# SonarControl.net
KiCad netlist of a schematic drawn in Altium Designer
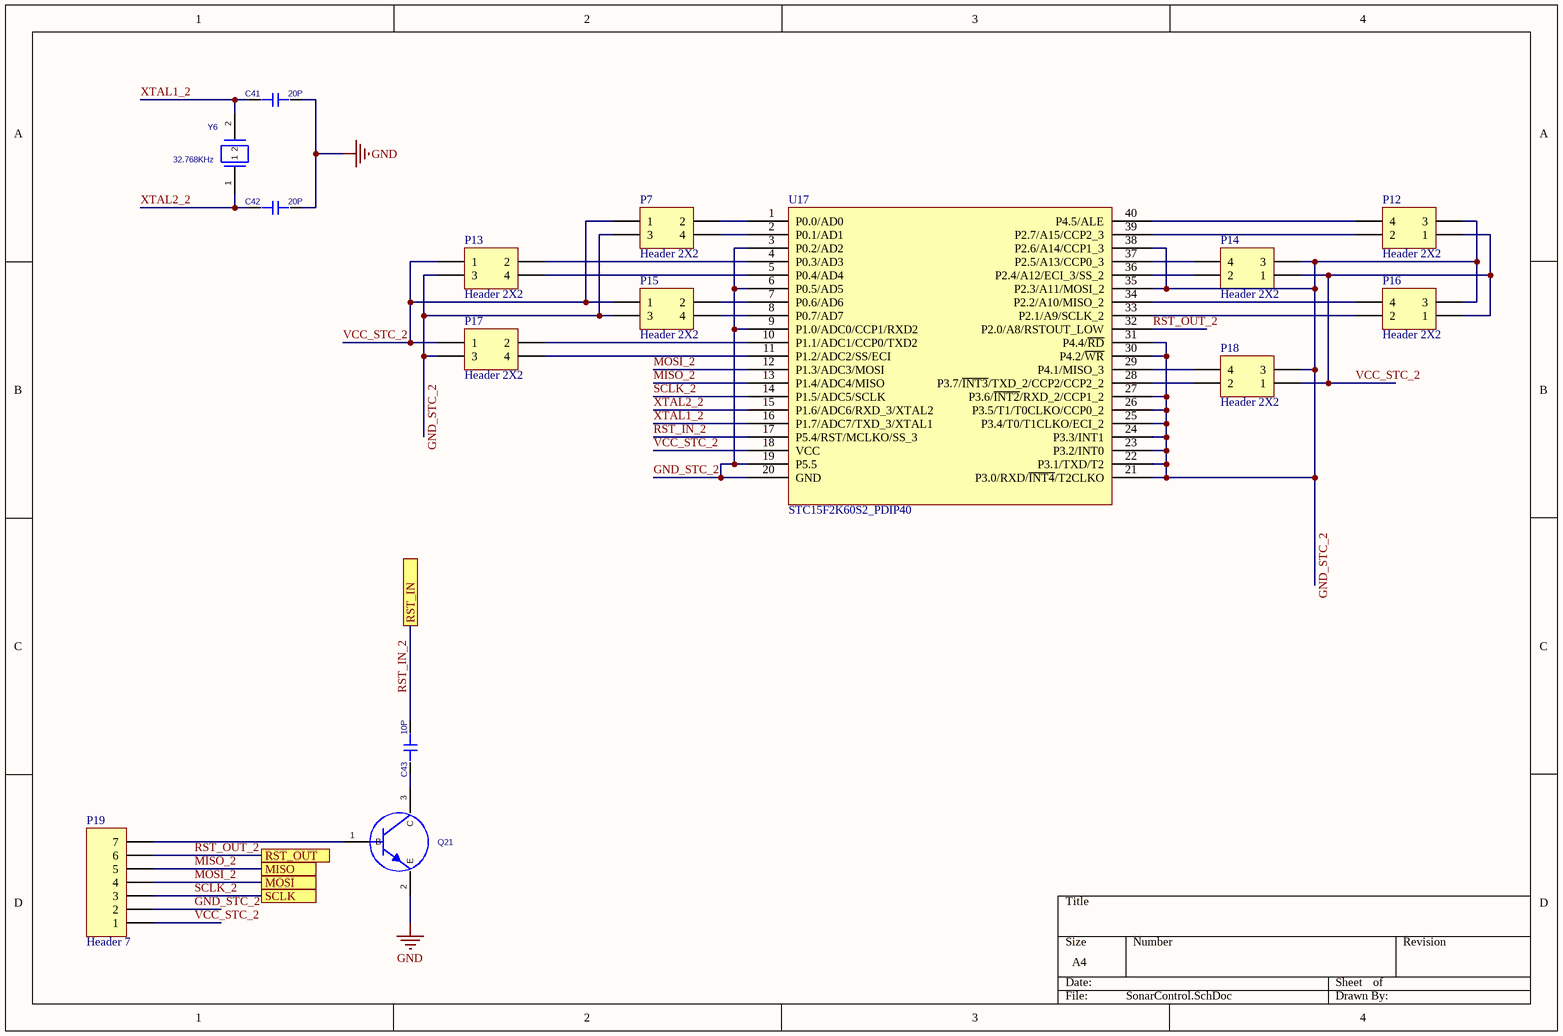
[diagram p0: SonarControl.SchDoc]

(export (version "E")
  (design (tool "Eeschema 10.0.6"))
  (components
    (comp (ref "C41")
      (value "20P")
      (footprint "CAP_0603_FIRE")
      (fields (field (name "Comment") "CAP_20P_0603_FIRE"))
      (libsource (lib "MINI-V3") (part "CAP_20P_0603_FIRE"))
    )
    (comp (ref "C42")
      (value "20P")
      (footprint "CAP_0603_FIRE")
      (fields (field (name "Comment") "CAP_20P_0603_FIRE"))
      (libsource (lib "MINI-V3") (part "CAP_20P_0603_FIRE"))
    )
    (comp (ref "C43")
      (value "10P")
      (footprint "RES_0603_FIRE")
      (description "0603")
      (fields (field (name "TOLERANCE") "+-5%") (field (name "Comment") "CAP_10P_0603_FIRE"))
      (libsource (lib "MINI-V3") (part "CAP_10P_0603_FIRE"))
    )
    (comp (ref "P7")
      (value "Header 2X2")
      (footprint "HDR2X2")
      (description "Header, 2-Pin, Dual row")
      (fields (field (name "PUBLISHER") "Altium Limited"))
      (libsource (lib "插针") (part "Header 2X2"))
    )
    (comp (ref "P12")
      (value "Header 2X2")
      (footprint "HDR2X2")
      (description "Header, 2-Pin, Dual row")
      (fields (field (name "PUBLISHER") "Altium Limited"))
      (libsource (lib "") (part "Header 2X2_1"))
    )
    (comp (ref "P13")
      (value "Header 2X2")
      (footprint "HDR2X2")
      (description "Header, 2-Pin, Dual row")
      (fields (field (name "PUBLISHER") "Altium Limited"))
      (libsource (lib "插针") (part "Header 2X2"))
    )
    (comp (ref "P14")
      (value "Header 2X2")
      (footprint "HDR2X2")
      (description "Header, 2-Pin, Dual row")
      (fields (field (name "PUBLISHER") "Altium Limited"))
      (libsource (lib "") (part "Header 2X2_1"))
    )
    (comp (ref "P15")
      (value "Header 2X2")
      (footprint "HDR2X2")
      (description "Header, 2-Pin, Dual row")
      (fields (field (name "PUBLISHER") "Altium Limited"))
      (libsource (lib "插针") (part "Header 2X2"))
    )
    (comp (ref "P16")
      (value "Header 2X2")
      (footprint "HDR2X2")
      (description "Header, 2-Pin, Dual row")
      (fields (field (name "PUBLISHER") "Altium Limited"))
      (libsource (lib "") (part "Header 2X2_1"))
    )
    (comp (ref "P17")
      (value "Header 2X2")
      (footprint "HDR2X2")
      (description "Header, 2-Pin, Dual row")
      (fields (field (name "PUBLISHER") "Altium Limited"))
      (libsource (lib "插针") (part "Header 2X2"))
    )
    (comp (ref "P18")
      (value "Header 2X2")
      (footprint "HDR2X2")
      (description "Header, 2-Pin, Dual row")
      (fields (field (name "PUBLISHER") "Altium Limited"))
      (libsource (lib "") (part "Header 2X2_1"))
    )
    (comp (ref "P19")
      (value "Header 7")
      (description "Header, 7-Pin")
      (fields (field (name "PUBLISHER") "Altium Limited"))
      (libsource (lib "插针") (part "Header 7"))
    )
    (comp (ref "Q21")
      (value "8050")
      (footprint "SOT-23")
      (description "NPN")
      (libsource (lib "MINI-V3") (part "8050"))
    )
    (comp (ref "U17")
      (value "STC15F2K60S2_PDIP40")
      (footprint "DIP40")
      (libsource (lib "STCMCU") (part "STC15F2K60S2_PDIP40"))
    )
    (comp (ref "Y6")
      (value "32.768KHz")
      (footprint "3215")
      (description "CRYSTAL")
      (fields (field (name "Comment") "XTAL_32.768KHZ_3215"))
      (libsource (lib "MINI-V3") (part "XTAL_32.768KHZ_3215"))
    )
  )
  (nets
    (net (code "1") (name "/GND_STC_2") (class "Default")
      (node (ref "P12") (pin "3") (pinfunction "3_3") (pintype "passive"))
      (node (ref "P13") (pin "3") (pinfunction "3_3") (pintype "passive"))
      (node (ref "P14") (pin "3") (pinfunction "3_3") (pintype "passive"))
      (node (ref "P15") (pin "3") (pinfunction "3_3") (pintype "passive"))
      (node (ref "P16") (pin "3") (pinfunction "3_3") (pintype "passive"))
      (node (ref "P17") (pin "3") (pinfunction "3_3") (pintype "passive"))
      (node (ref "P18") (pin "3") (pinfunction "3_3") (pintype "passive"))
      (node (ref "P19") (pin "2") (pinfunction "2_2") (pintype "passive"))
      (node (ref "P7") (pin "3") (pinfunction "3_3") (pintype "passive"))
      (node (ref "U17") (pin "19") (pinfunction "P5.5_19") (pintype "passive"))
      (node (ref "U17") (pin "20") (pinfunction "GND_20") (pintype "passive"))
      (node (ref "U17") (pin "21") (pinfunction "P3.0/RXD/~{INT4}/T2CLKO_21") (pintype "passive"))
      (node (ref "U17") (pin "22") (pinfunction "P3.1/TXD/T2_22") (pintype "passive"))
      (node (ref "U17") (pin "23") (pinfunction "P3.2/INT0_23") (pintype "passive"))
      (node (ref "U17") (pin "24") (pinfunction "P3.3/INT1_24") (pintype "passive"))
      (node (ref "U17") (pin "25") (pinfunction "P3.4/T0/T1CLKO/ECI_2_25") (pintype "passive"))
      (node (ref "U17") (pin "26") (pinfunction "P3.5/T1/T0CLKO/CCP0_2_26") (pintype "passive"))
      (node (ref "U17") (pin "27") (pinfunction "P3.6/~{INT2}/RXD_2/CCP1_2_27") (pintype "passive"))
      (node (ref "U17") (pin "3") (pinfunction "P0.2/AD2_3") (pintype "passive"))
      (node (ref "U17") (pin "30") (pinfunction "P4.2/~{WR}_30") (pintype "passive"))
      (node (ref "U17") (pin "31") (pinfunction "P4.4/~{RD}_31") (pintype "passive"))
      (node (ref "U17") (pin "35") (pinfunction "P2.3/A11/MOSI_2_35") (pintype "passive"))
      (node (ref "U17") (pin "38") (pinfunction "P2.6/A14/CCP1_3_38") (pintype "passive"))
      (node (ref "U17") (pin "6") (pinfunction "P0.5/AD5_6") (pintype "passive"))
      (node (ref "U17") (pin "9") (pinfunction "P1.0/ADC0/CCP1/RXD2_9") (pintype "passive"))
    )
    (net (code "2") (name "/MISO_2") (class "Default")
      (node (ref "P19") (pin "5") (pinfunction "5_5") (pintype "passive"))
      (node (ref "U17") (pin "13") (pinfunction "P1.4/ADC4/MISO_13") (pintype "passive"))
    )
    (net (code "3") (name "/MOSI_2") (class "Default")
      (node (ref "P19") (pin "4") (pinfunction "4_4") (pintype "passive"))
      (node (ref "U17") (pin "12") (pinfunction "P1.3/ADC3/MOSI_12") (pintype "passive"))
    )
    (net (code "4") (name "/RST_IN_2") (class "Default")
      (node (ref "C43") (pin "2") (pinfunction "2_2") (pintype "passive"))
      (node (ref "U17") (pin "17") (pinfunction "P5.4/RST/MCLKO/SS_3_17") (pintype "passive"))
    )
    (net (code "5") (name "/RST_OUT_2") (class "Default")
      (node (ref "P19") (pin "6") (pinfunction "6_6") (pintype "passive"))
      (node (ref "U17") (pin "32") (pinfunction "P2.0/A8/RSTOUT_LOW_32") (pintype "passive"))
    )
    (net (code "6") (name "/SCLK_2") (class "Default")
      (node (ref "P19") (pin "3") (pinfunction "3_3") (pintype "passive"))
      (node (ref "U17") (pin "14") (pinfunction "P1.5/ADC5/SCLK_14") (pintype "passive"))
    )
    (net (code "7") (name "/VCC_STC_2") (class "Default")
      (node (ref "P12") (pin "1") (pinfunction "1_1") (pintype "passive"))
      (node (ref "P13") (pin "1") (pinfunction "1_1") (pintype "passive"))
      (node (ref "P14") (pin "1") (pinfunction "1_1") (pintype "passive"))
      (node (ref "P15") (pin "1") (pinfunction "1_1") (pintype "passive"))
      (node (ref "P16") (pin "1") (pinfunction "1_1") (pintype "passive"))
      (node (ref "P17") (pin "1") (pinfunction "1_1") (pintype "passive"))
      (node (ref "P18") (pin "1") (pinfunction "1_1") (pintype "passive"))
      (node (ref "P19") (pin "1") (pinfunction "1_1") (pintype "passive"))
      (node (ref "P7") (pin "1") (pinfunction "1_1") (pintype "passive"))
      (node (ref "U17") (pin "18") (pinfunction "VCC_18") (pintype "passive"))
    )
    (net (code "8") (name "/XTAL1_2") (class "Default")
      (node (ref "C41") (pin "1") (pinfunction "1_1") (pintype "passive"))
      (node (ref "U17") (pin "16") (pinfunction "P1.7/ADC7/TXD_3/XTAL1_16") (pintype "passive"))
      (node (ref "Y6") (pin "2") (pinfunction "2_2") (pintype "passive"))
    )
    (net (code "9") (name "/XTAL2_2") (class "Default")
      (node (ref "C42") (pin "1") (pinfunction "1_1") (pintype "passive"))
      (node (ref "U17") (pin "15") (pinfunction "P1.6/ADC6/RXD_3/XTAL2_15") (pintype "passive"))
      (node (ref "Y6") (pin "1") (pinfunction "1_1") (pintype "passive"))
    )
    (net (code "10") (name "GND") (class "Default")
      (node (ref "C41") (pin "2") (pinfunction "2_2") (pintype "passive"))
      (node (ref "C42") (pin "2") (pinfunction "2_2") (pintype "passive"))
      (node (ref "Q21") (pin "2") (pinfunction "E_2") (pintype "passive"))
    )
    (net (code "11") (name "Net-(Q21-B)") (class "Default")
      (node (ref "P19") (pin "7") (pinfunction "7_7") (pintype "passive"))
      (node (ref "Q21") (pin "1") (pinfunction "B_1") (pintype "passive"))
    )
    (net (code "12") (name "Net-(Q21-C)") (class "Default")
      (node (ref "C43") (pin "1") (pinfunction "1_1") (pintype "passive"))
      (node (ref "Q21") (pin "3") (pinfunction "C_3") (pintype "passive"))
    )
    (net (code "13") (name "Net-(U17-P0.0{slash}AD0)") (class "Default")
      (node (ref "P7") (pin "2") (pinfunction "2_2") (pintype "passive"))
      (node (ref "U17") (pin "1") (pinfunction "P0.0/AD0_1") (pintype "passive"))
    )
    (net (code "14") (name "Net-(U17-P0.1{slash}AD1)") (class "Default")
      (node (ref "P7") (pin "4") (pinfunction "4_4") (pintype "passive"))
      (node (ref "U17") (pin "2") (pinfunction "P0.1/AD1_2") (pintype "passive"))
    )
    (net (code "15") (name "Net-(U17-P0.3{slash}AD3)") (class "Default")
      (node (ref "P13") (pin "2") (pinfunction "2_2") (pintype "passive"))
      (node (ref "U17") (pin "4") (pinfunction "P0.3/AD3_4") (pintype "passive"))
    )
    (net (code "16") (name "Net-(U17-P0.4{slash}AD4)") (class "Default")
      (node (ref "P13") (pin "4") (pinfunction "4_4") (pintype "passive"))
      (node (ref "U17") (pin "5") (pinfunction "P0.4/AD4_5") (pintype "passive"))
    )
    (net (code "17") (name "Net-(U17-P0.6{slash}AD6)") (class "Default")
      (node (ref "P15") (pin "2") (pinfunction "2_2") (pintype "passive"))
      (node (ref "U17") (pin "7") (pinfunction "P0.6/AD6_7") (pintype "passive"))
    )
    (net (code "18") (name "Net-(U17-P0.7{slash}AD7)") (class "Default")
      (node (ref "P15") (pin "4") (pinfunction "4_4") (pintype "passive"))
      (node (ref "U17") (pin "8") (pinfunction "P0.7/AD7_8") (pintype "passive"))
    )
    (net (code "19") (name "Net-(U17-P1.1{slash}ADC1{slash}CCP0{slash}TXD2)") (class "Default")
      (node (ref "P17") (pin "2") (pinfunction "2_2") (pintype "passive"))
      (node (ref "U17") (pin "10") (pinfunction "P1.1/ADC1/CCP0/TXD2_10") (pintype "passive"))
    )
    (net (code "20") (name "Net-(U17-P1.2{slash}ADC2{slash}SS{slash}ECI)") (class "Default")
      (node (ref "P17") (pin "4") (pinfunction "4_4") (pintype "passive"))
      (node (ref "U17") (pin "11") (pinfunction "P1.2/ADC2/SS/ECI_11") (pintype "passive"))
    )
    (net (code "21") (name "Net-(U17-P2.1{slash}A9{slash}SCLK_2)") (class "Default")
      (node (ref "P16") (pin "2") (pinfunction "2_2") (pintype "passive"))
      (node (ref "U17") (pin "33") (pinfunction "P2.1/A9/SCLK_2_33") (pintype "passive"))
    )
    (net (code "22") (name "Net-(U17-P2.2{slash}A10{slash}MISO_2)") (class "Default")
      (node (ref "P16") (pin "4") (pinfunction "4_4") (pintype "passive"))
      (node (ref "U17") (pin "34") (pinfunction "P2.2/A10/MISO_2_34") (pintype "passive"))
    )
    (net (code "23") (name "Net-(U17-P2.4{slash}A12{slash}ECI_3{slash}SS_2)") (class "Default")
      (node (ref "P14") (pin "2") (pinfunction "2_2") (pintype "passive"))
      (node (ref "U17") (pin "36") (pinfunction "P2.4/A12/ECI_3/SS_2_36") (pintype "passive"))
    )
    (net (code "24") (name "Net-(U17-P2.5{slash}A13{slash}CCP0_3)") (class "Default")
      (node (ref "P14") (pin "4") (pinfunction "4_4") (pintype "passive"))
      (node (ref "U17") (pin "37") (pinfunction "P2.5/A13/CCP0_3_37") (pintype "passive"))
    )
    (net (code "25") (name "Net-(U17-P2.7{slash}A15{slash}CCP2_3)") (class "Default")
      (node (ref "P12") (pin "2") (pinfunction "2_2") (pintype "passive"))
      (node (ref "U17") (pin "39") (pinfunction "P2.7/A15/CCP2_3_39") (pintype "passive"))
    )
    (net (code "26") (name "Net-(U17-P3.7{slash}~{INT3}{slash}TXD_2{slash}CCP2{slash}CCP2_2)") (class "Default")
      (node (ref "P18") (pin "2") (pinfunction "2_2") (pintype "passive"))
      (node (ref "U17") (pin "28") (pinfunction "P3.7/~{INT3}/TXD_2/CCP2/CCP2_2_28") (pintype "passive"))
    )
    (net (code "27") (name "Net-(U17-P4.1{slash}MISO_3)") (class "Default")
      (node (ref "P18") (pin "4") (pinfunction "4_4") (pintype "passive"))
      (node (ref "U17") (pin "29") (pinfunction "P4.1/MISO_3_29") (pintype "passive"))
    )
    (net (code "28") (name "Net-(U17-P4.5{slash}ALE)") (class "Default")
      (node (ref "P12") (pin "4") (pinfunction "4_4") (pintype "passive"))
      (node (ref "U17") (pin "40") (pinfunction "P4.5/ALE_40") (pintype "passive"))
    )
  )
)
